# design.net
KiCad netlist of a schematic drawn in EasyEDA Pro
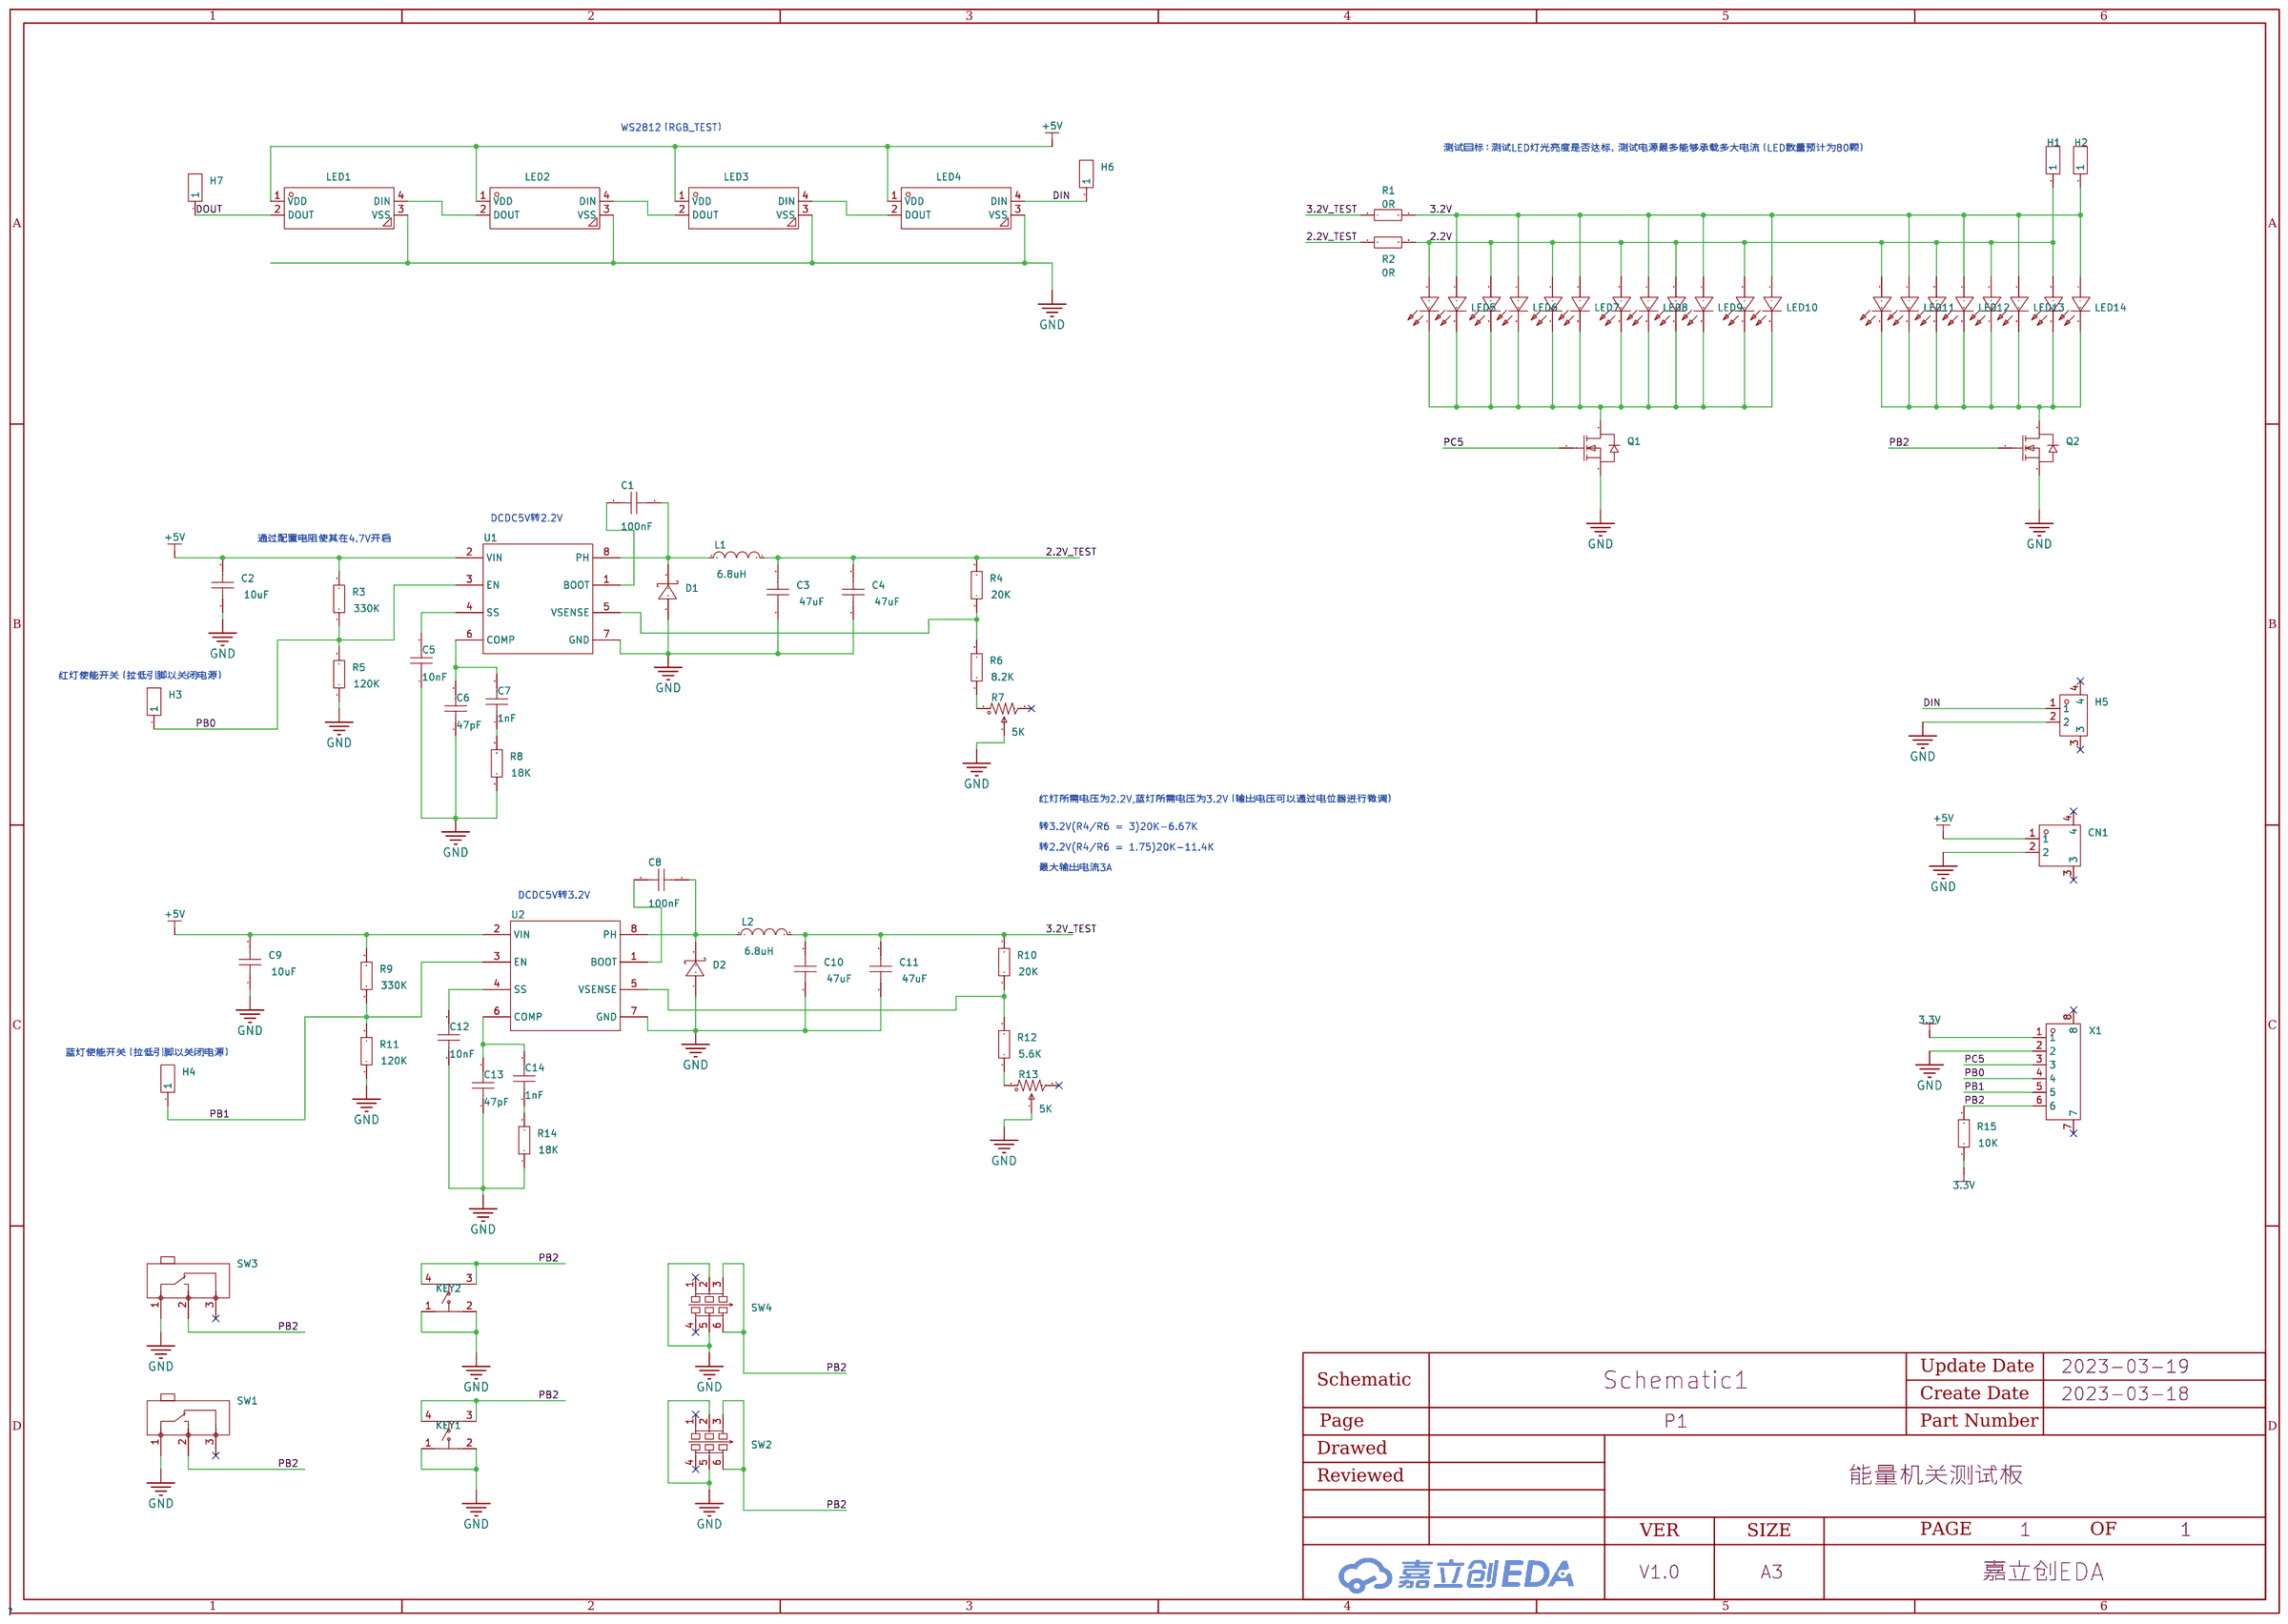
[diagram p0: schematic sheet]

(export (version "E")
  (design (tool "Eeschema 10.0.6"))
  (components
    (comp (ref "C1")
      (value "100nF")
      (footprint "easyedapro:C0603")
      (libsource (lib "easyedapro") (part "CapAcitance"))
    )
    (comp (ref "C2")
      (value "10uF")
      (footprint "easyedapro:C0603")
      (description "容值:10uF;精度:±20%;额定电压:25V;材质(温度系数):X5R;")
      (fields
        (field (name "Manufacturer Part") "CL10A106MA8NRNC")
        (field (name "Manufacturer") "SAMSUNG(三星)")
      )
      (libsource (lib "easyedapro") (part "CL10A106MA8NRNC"))
    )
    (comp (ref "C3")
      (value "47uF")
      (footprint "easyedapro:C1206")
      (description "容值:47uF;精度:±20%;额定电压:10V;材质(温度系数):X5R;")
      (fields
        (field (name "Manufacturer Part") "CL31A476MPHNNNE")
        (field (name "Manufacturer") "SAMSUNG(三星)")
      )
      (libsource (lib "easyedapro") (part "CL31A476MPHNNNE"))
    )
    (comp (ref "C4")
      (value "47uF")
      (footprint "easyedapro:C1206")
      (description "容值:47uF;精度:±20%;额定电压:10V;材质(温度系数):X5R;")
      (fields
        (field (name "Manufacturer Part") "CL31A476MPHNNNE")
        (field (name "Manufacturer") "SAMSUNG(三星)")
      )
      (libsource (lib "easyedapro") (part "CL31A476MPHNNNE"))
    )
    (comp (ref "C5")
      (value "10nF")
      (footprint "easyedapro:C0603")
      (libsource (lib "easyedapro") (part "CapAcitance"))
    )
    (comp (ref "C6")
      (value "47pF")
      (footprint "easyedapro:C0603")
      (libsource (lib "easyedapro") (part "CapAcitance"))
    )
    (comp (ref "C7")
      (value "1nF")
      (footprint "easyedapro:C0603")
      (libsource (lib "easyedapro") (part "CapAcitance"))
    )
    (comp (ref "C8")
      (value "100nF")
      (footprint "easyedapro:C0603")
      (libsource (lib "easyedapro") (part "CapAcitance"))
    )
    (comp (ref "C9")
      (value "10uF")
      (footprint "easyedapro:C0603")
      (libsource (lib "easyedapro") (part "CapAcitance"))
    )
    (comp (ref "C10")
      (value "47uF")
      (footprint "easyedapro:C1206")
      (description "容值:47uF;精度:±20%;额定电压:10V;材质(温度系数):X5R;")
      (fields
        (field (name "Manufacturer Part") "CL31A476MPHNNNE")
        (field (name "Manufacturer") "SAMSUNG(三星)")
      )
      (libsource (lib "easyedapro") (part "CL31A476MPHNNNE"))
    )
    (comp (ref "C11")
      (value "47uF")
      (footprint "easyedapro:C1206")
      (description "容值:47uF;精度:±20%;额定电压:10V;材质(温度系数):X5R;")
      (fields
        (field (name "Manufacturer Part") "CL31A476MPHNNNE")
        (field (name "Manufacturer") "SAMSUNG(三星)")
      )
      (libsource (lib "easyedapro") (part "CL31A476MPHNNNE"))
    )
    (comp (ref "C12")
      (value "10nF")
      (footprint "easyedapro:C0603")
      (libsource (lib "easyedapro") (part "CapAcitance"))
    )
    (comp (ref "C13")
      (value "47pF")
      (footprint "easyedapro:C0603")
      (libsource (lib "easyedapro") (part "CapAcitance"))
    )
    (comp (ref "C14")
      (value "1nF")
      (footprint "easyedapro:C0603")
      (libsource (lib "easyedapro") (part "CapAcitance"))
    )
    (comp (ref "CN1")
      (value "XT30PW-M")
      (footprint "easyedapro:CONN-TH_XT30PW-M")
      (description "Socket,DCsupply,XT30,male,PIN:2")
      (fields (field (name "Manufacturer") "AMASS(艾迈斯)"))
      (libsource (lib "easyedapro") (part "XT30PW-M"))
    )
    (comp (ref "D1")
      (value "SS54")
      (footprint "easyedapro:SMA_L4.4-W2.8-LS5.4-R-RD")
      (description "直流反向耐压(Vr):40V;平均整流电流(Io):5A;正向压降(Vf):550mV@5A;")
      (fields (field (name "Manufacturer") "MDD"))
      (libsource (lib "easyedapro") (part "SS54_C22452"))
    )
    (comp (ref "D2")
      (value "SS54")
      (footprint "easyedapro:SMA_L4.4-W2.8-LS5.4-R-RD")
      (description "直流反向耐压(Vr):40V;平均整流电流(Io):5A;正向压降(Vf):550mV@5A;")
      (fields (field (name "Manufacturer") "MDD"))
      (libsource (lib "easyedapro") (part "SS54_C22452"))
    )
    (comp (ref "H1")
      (value "~")
      (footprint "easyedapro:HDR-TH_1P-V-M_XKB_X4611WV-01I-C28D40")
      (libsource (lib "easyedapro") (part "HDR_1x1"))
    )
    (comp (ref "H2")
      (value "~")
      (footprint "easyedapro:HDR-TH_1P-V-M_XKB_X4611WV-01I-C28D40")
      (libsource (lib "easyedapro") (part "HDR_1x1"))
    )
    (comp (ref "H3")
      (value "~")
      (footprint "easyedapro:HDR-TH_1P-V-M_XKB_X4611WV-01I-C28D40")
      (libsource (lib "easyedapro") (part "HDR_1x1"))
    )
    (comp (ref "H4")
      (value "~")
      (footprint "easyedapro:HDR-TH_1P-V-M_XKB_X4611WV-01I-C28D40")
      (libsource (lib "easyedapro") (part "HDR_1x1"))
    )
    (comp (ref "H5")
      (value "GH1.25-2PWBPZ")
      (footprint "easyedapro:CONN-SMD_GH1.25-2PWBPZ")
      (fields (field (name "Manufacturer") "BOOMELE(博穆精密)"))
      (libsource (lib "easyedapro") (part "GH1.25-2PWBPZ"))
    )
    (comp (ref "H6")
      (value "~")
      (footprint "easyedapro:HDR-TH_1P-V-M_XKB_X4611WV-01I-C28D40")
      (libsource (lib "easyedapro") (part "HDR_1x1"))
    )
    (comp (ref "H7")
      (value "~")
      (footprint "easyedapro:HDR-TH_1P-V-M_XKB_X4611WV-01I-C28D40")
      (libsource (lib "easyedapro") (part "HDR_1x1"))
    )
    (comp (ref "KEY1")
      (value "B3F-4055")
      (footprint "easyedapro:KEY-TH_4P-L12.0-W12.0-P5.00-LS13.4-EH")
      (description "触点电流:50mA;额定电压(DC):24V;电路结构:单刀单掷;安装方式:直插;按钮形状:方形按钮;带灯:-;开关长度:12mm;开关宽度:12mm;开关高度:7.3mm;")
      (fields (field (name "Manufacturer") "OMRON(欧姆龙)"))
      (libsource (lib "easyedapro") (part "B3F-4055"))
    )
    (comp (ref "KEY2")
      (value "B3F-4055")
      (footprint "easyedapro:KEY-TH_4P-L12.0-W12.0-P5.00-LS13.4-EH")
      (description "触点电流:50mA;额定电压(DC):24V;电路结构:单刀单掷;安装方式:直插;按钮形状:方形按钮;带灯:-;开关长度:12mm;开关宽度:12mm;开关高度:7.3mm;")
      (fields (field (name "Manufacturer") "OMRON(欧姆龙)"))
      (libsource (lib "easyedapro") (part "B3F-4055"))
    )
    (comp (ref "L1")
      (value "6.8uH")
      (footprint "easyedapro:IND-SMD_L4.4-W4.2")
      (description "电感值:6.8uH;精度:±20%;额定电流:-;直流电阻(DCR):-;")
      (fields
        (field (name "Manufacturer Part") "SLO0420H6R8MTT")
        (field (name "Manufacturer") "Sunltech(韩国顺磁)")
      )
      (libsource (lib "easyedapro") (part "SLO0420H6R8MTT"))
    )
    (comp (ref "L2")
      (value "6.8uH")
      (footprint "easyedapro:IND-SMD_L4.4-W4.2")
      (description "电感值:6.8uH;精度:±20%;额定电流:-;直流电阻(DCR):-;")
      (fields
        (field (name "Manufacturer Part") "SLO0420H6R8MTT")
        (field (name "Manufacturer") "Sunltech(韩国顺磁)")
      )
      (libsource (lib "easyedapro") (part "SLO0420H6R8MTT"))
    )
    (comp (ref "LED1")
      (value "WS2812E")
      (footprint "easyedapro:LED-SMD_4P-L5.0-W5.0-BL_TC5050RGB")
      (description "发光颜色:RGB三色;透镜颜色:无色透明;")
      (fields (field (name "Manufacturer") "worldsemi"))
      (libsource (lib "easyedapro") (part "WS2812E"))
    )
    (comp (ref "LED2")
      (value "WS2812E")
      (footprint "easyedapro:LED-SMD_4P-L5.0-W5.0-BL_TC5050RGB")
      (description "发光颜色:RGB三色;透镜颜色:无色透明;")
      (fields (field (name "Manufacturer") "worldsemi"))
      (libsource (lib "easyedapro") (part "WS2812E"))
    )
    (comp (ref "LED3")
      (value "WS2812E")
      (footprint "easyedapro:LED-SMD_4P-L5.0-W5.0-BL_TC5050RGB")
      (description "发光颜色:RGB三色;透镜颜色:无色透明;")
      (fields (field (name "Manufacturer") "worldsemi"))
      (libsource (lib "easyedapro") (part "WS2812E"))
    )
    (comp (ref "LED4")
      (value "WS2812E")
      (footprint "easyedapro:LED-SMD_4P-L5.0-W5.0-BL_TC5050RGB")
      (description "发光颜色:RGB三色;透镜颜色:无色透明;")
      (fields (field (name "Manufacturer") "worldsemi"))
      (libsource (lib "easyedapro") (part "WS2812E"))
    )
    (comp (ref "LED5")
      (value "XL-3528SURUBC")
      (footprint "easyedapro:LED-SMD_4P-L3.2-W2.8-LS3.5-TL")
      (fields (field (name "Manufacturer") "XINGLIGHT(成兴光)"))
      (libsource (lib "easyedapro") (part "XL-3528SURUBC"))
    )
    (comp (ref "LED6")
      (value "XL-3528SURUBC")
      (footprint "easyedapro:LED-SMD_4P-L3.2-W2.8-LS3.5-TL")
      (fields (field (name "Manufacturer") "XINGLIGHT(成兴光)"))
      (libsource (lib "easyedapro") (part "XL-3528SURUBC"))
    )
    (comp (ref "LED7")
      (value "XL-3528SURUBC")
      (footprint "easyedapro:LED-SMD_4P-L3.2-W2.8-LS3.5-TL")
      (fields (field (name "Manufacturer") "XINGLIGHT(成兴光)"))
      (libsource (lib "easyedapro") (part "XL-3528SURUBC"))
    )
    (comp (ref "LED8")
      (value "XL-3528SURUBC")
      (footprint "easyedapro:LED-SMD_4P-L3.2-W2.8-LS3.5-TL")
      (fields (field (name "Manufacturer") "XINGLIGHT(成兴光)"))
      (libsource (lib "easyedapro") (part "XL-3528SURUBC"))
    )
    (comp (ref "LED9")
      (value "XL-3528SURUBC")
      (footprint "easyedapro:LED-SMD_4P-L3.2-W2.8-LS3.5-TL")
      (fields (field (name "Manufacturer") "XINGLIGHT(成兴光)"))
      (libsource (lib "easyedapro") (part "XL-3528SURUBC"))
    )
    (comp (ref "LED10")
      (value "XL-3528SURUBC")
      (footprint "easyedapro:LED-SMD_4P-L3.2-W2.8-LS3.5-TL")
      (fields (field (name "Manufacturer") "XINGLIGHT(成兴光)"))
      (libsource (lib "easyedapro") (part "XL-3528SURUBC"))
    )
    (comp (ref "LED11")
      (value "XL-3528SURUBC")
      (footprint "easyedapro:LED-SMD_4P-L3.2-W2.8-LS3.5-TL")
      (fields (field (name "Manufacturer") "XINGLIGHT(成兴光)"))
      (libsource (lib "easyedapro") (part "XL-3528SURUBC"))
    )
    (comp (ref "LED12")
      (value "XL-3528SURUBC")
      (footprint "easyedapro:LED-SMD_4P-L3.2-W2.8-LS3.5-TL")
      (fields (field (name "Manufacturer") "XINGLIGHT(成兴光)"))
      (libsource (lib "easyedapro") (part "XL-3528SURUBC"))
    )
    (comp (ref "LED13")
      (value "XL-3528SURUBC")
      (footprint "easyedapro:LED-SMD_4P-L3.2-W2.8-LS3.5-TL")
      (fields (field (name "Manufacturer") "XINGLIGHT(成兴光)"))
      (libsource (lib "easyedapro") (part "XL-3528SURUBC"))
    )
    (comp (ref "LED14")
      (value "XL-3528SURUBC")
      (footprint "easyedapro:LED-SMD_4P-L3.2-W2.8-LS3.5-TL")
      (fields (field (name "Manufacturer") "XINGLIGHT(成兴光)"))
      (libsource (lib "easyedapro") (part "XL-3528SURUBC"))
    )
    (comp (ref "Q1")
      (value "AO3400A")
      (footprint "easyedapro:SOT-23-3_L2.9-W1.6-P1.90-LS2.8-BR")
      (fields (field (name "Manufacturer") "AOS"))
      (libsource (lib "easyedapro") (part "AO3400A"))
    )
    (comp (ref "Q2")
      (value "AO3400A")
      (footprint "easyedapro:SOT-23-3_L2.9-W1.6-P1.90-LS2.8-BR")
      (fields (field (name "Manufacturer") "AOS"))
      (libsource (lib "easyedapro") (part "AO3400A"))
    )
    (comp (ref "R1") (value "0R") (footprint "easyedapro:R0603") (libsource (lib "easyedapro") (part "电阻")))
    (comp (ref "R2") (value "0R") (footprint "easyedapro:R0603") (libsource (lib "easyedapro") (part "电阻")))
    (comp (ref "R3") (value "330K") (footprint "easyedapro:R0603") (libsource (lib "easyedapro") (part "电阻")))
    (comp (ref "R4") (value "20K") (footprint "easyedapro:R0603") (libsource (lib "easyedapro") (part "电阻")))
    (comp (ref "R5") (value "120K") (footprint "easyedapro:R0603") (libsource (lib "easyedapro") (part "电阻")))
    (comp (ref "R6") (value "8.2K") (footprint "easyedapro:R0603") (libsource (lib "easyedapro") (part "电阻")))
    (comp (ref "R7")
      (value "5K")
      (footprint "easyedapro:RES-ADJ-SMD_3P-L3.0-W3.8-P1.75-BR")
      (description "阻值:10kΩ;精度:±25%;功率:150mW;圈数:-;额定电压:-;")
      (fields (field (name "Manufacturer Part") "TC33X-2-103E") (field (name "Manufacturer") "BOURNS"))
      (libsource (lib "easyedapro") (part "TC33X-2-103E"))
    )
    (comp (ref "R8") (value "18K") (footprint "easyedapro:R0603") (libsource (lib "easyedapro") (part "电阻")))
    (comp (ref "R9") (value "330K") (footprint "easyedapro:R0603") (libsource (lib "easyedapro") (part "电阻")))
    (comp (ref "R10") (value "20K") (footprint "easyedapro:R0603") (libsource (lib "easyedapro") (part "电阻")))
    (comp (ref "R11")
      (value "120K")
      (footprint "easyedapro:R0603")
      (libsource (lib "easyedapro") (part "电阻"))
    )
    (comp (ref "R12")
      (value "5.6K")
      (footprint "easyedapro:R0603")
      (libsource (lib "easyedapro") (part "电阻"))
    )
    (comp (ref "R13")
      (value "5K")
      (footprint "easyedapro:RES-ADJ-SMD_3P-L3.0-W3.8-P1.75-BR")
      (description "阻值:10kΩ;精度:±25%;功率:150mW;圈数:-;额定电压:-;")
      (fields (field (name "Manufacturer Part") "TC33X-2-103E") (field (name "Manufacturer") "BOURNS"))
      (libsource (lib "easyedapro") (part "TC33X-2-103E"))
    )
    (comp (ref "R14") (value "18K") (footprint "easyedapro:R0603") (libsource (lib "easyedapro") (part "电阻")))
    (comp (ref "R15") (value "10K") (footprint "easyedapro:R0603") (libsource (lib "easyedapro") (part "电阻")))
    (comp (ref "SW1")
      (value "D2F-F")
      (footprint "easyedapro:SW-TH_D2F-F")
      (description "额定电流(DC):-;额定电压(DC):-;额定电流(AC):1A;额定电压(AC):125V;电路结构:单刀双掷;")
      (fields (field (name "Manufacturer") "OMRON(欧姆龙)"))
      (libsource (lib "easyedapro") (part "D2F-F"))
    )
    (comp (ref "SW2")
      (value "BTSA-L-P-16")
      (footprint "easyedapro:SW-TH_BTSA-X-P-16")
      (fields (field (name "Manufacturer") "ROCPU Switches(台普)"))
      (libsource (lib "easyedapro") (part "BTSA-L-P-16"))
    )
    (comp (ref "SW3")
      (value "D2F-F")
      (footprint "easyedapro:SW-TH_D2F-F")
      (description "额定电流(DC):-;额定电压(DC):-;额定电流(AC):1A;额定电压(AC):125V;电路结构:单刀双掷;")
      (fields (field (name "Manufacturer") "OMRON(欧姆龙)"))
      (libsource (lib "easyedapro") (part "D2F-F"))
    )
    (comp (ref "SW4")
      (value "BTSA-L-P-16")
      (footprint "easyedapro:SW-TH_BTSA-X-P-16")
      (fields (field (name "Manufacturer") "ROCPU Switches(台普)"))
      (libsource (lib "easyedapro") (part "BTSA-L-P-16"))
    )
    (comp (ref "U1")
      (value "TPS54331DR")
      (footprint "easyedapro:SOIC-8_L5.0-W4.0-P1.27-LS6.0-BL")
      (description "功能类型:降压型;同步整流:-;输出通道数:-;拓扑结构:-;输入电压:-;输出电流(最大值):-;开关频率:-;")
      (fields (field (name "Manufacturer") "TI(德州仪器)"))
      (libsource (lib "easyedapro") (part "TPS54331DR"))
    )
    (comp (ref "U2")
      (value "TPS54331DR")
      (footprint "easyedapro:SOIC-8_L5.0-W4.0-P1.27-LS6.0-BL")
      (description "功能类型:降压型;同步整流:-;输出通道数:-;拓扑结构:-;输入电压:-;输出电流(最大值):-;开关频率:-;")
      (fields (field (name "Manufacturer") "TI(德州仪器)"))
      (libsource (lib "easyedapro") (part "TPS54331DR"))
    )
    (comp (ref "X1")
      (value "GH125-S06DCA-00")
      (footprint "easyedapro:CONN-SMD_6P-P1.25_JUSHUO_GH125-S06DCA-00")
      (description "参考系列:GH;间距:1.25mm;插针结构:1x6P;排数:1;每排PIN数:6;行距:-;公母:公型插针;安装方式:卧贴;额定电流:1A;工作温度范围:-25°C~+85°C;")
      (fields (field (name "Manufacturer") "JS(钜硕电子)"))
      (libsource (lib "easyedapro") (part "GH125-S06DCA-00"))
    )
  )
  (nets
    (net (code "1") (name "+5V") (class "Default")
      (node (ref "C2") (pin "2") (pinfunction "2_2") (pintype "input"))
      (node (ref "C9") (pin "2") (pinfunction "2_2") (pintype "input"))
      (node (ref "CN1") (pin "1") (pinfunction "1_1") (pintype "input"))
      (node (ref "LED1") (pin "1") (pinfunction "VDD_1") (pintype "input"))
      (node (ref "LED2") (pin "1") (pinfunction "VDD_1") (pintype "input"))
      (node (ref "LED3") (pin "1") (pinfunction "VDD_1") (pintype "input"))
      (node (ref "LED4") (pin "1") (pinfunction "VDD_1") (pintype "input"))
      (node (ref "R3") (pin "2") (pinfunction "2_2") (pintype "input"))
      (node (ref "R9") (pin "2") (pinfunction "2_2") (pintype "input"))
      (node (ref "U1") (pin "2") (pinfunction "VIN_2") (pintype "input"))
      (node (ref "U2") (pin "2") (pinfunction "VIN_2") (pintype "input"))
    )
    (net (code "2") (name "/2.2V") (class "Default")
      (node (ref "H1") (pin "1") (pinfunction "1_1") (pintype "unspecified"))
      (node (ref "LED10") (pin "2") (pinfunction "2_2") (pintype "input"))
      (node (ref "LED11") (pin "2") (pinfunction "2_2") (pintype "input"))
      (node (ref "LED12") (pin "2") (pinfunction "2_2") (pintype "input"))
      (node (ref "LED13") (pin "2") (pinfunction "2_2") (pintype "input"))
      (node (ref "LED14") (pin "2") (pinfunction "2_2") (pintype "input"))
      (node (ref "LED5") (pin "2") (pinfunction "2_2") (pintype "input"))
      (node (ref "LED6") (pin "2") (pinfunction "2_2") (pintype "input"))
      (node (ref "LED7") (pin "2") (pinfunction "2_2") (pintype "input"))
      (node (ref "LED8") (pin "2") (pinfunction "2_2") (pintype "input"))
      (node (ref "LED9") (pin "2") (pinfunction "2_2") (pintype "input"))
      (node (ref "R2") (pin "2") (pinfunction "2_2") (pintype "input"))
    )
    (net (code "3") (name "/2.2V_TEST") (class "Default")
      (node (ref "C3") (pin "2") (pinfunction "2_2") (pintype "input"))
      (node (ref "C4") (pin "2") (pinfunction "2_2") (pintype "input"))
      (node (ref "L1") (pin "2") (pinfunction "2_2") (pintype "input"))
      (node (ref "R2") (pin "1") (pinfunction "1_1") (pintype "input"))
      (node (ref "R4") (pin "2") (pinfunction "2_2") (pintype "input"))
    )
    (net (code "4") (name "/3.2V") (class "Default")
      (node (ref "H2") (pin "1") (pinfunction "1_1") (pintype "unspecified"))
      (node (ref "LED10") (pin "4") (pinfunction "4_4") (pintype "input"))
      (node (ref "LED11") (pin "4") (pinfunction "4_4") (pintype "input"))
      (node (ref "LED12") (pin "4") (pinfunction "4_4") (pintype "input"))
      (node (ref "LED13") (pin "4") (pinfunction "4_4") (pintype "input"))
      (node (ref "LED14") (pin "4") (pinfunction "4_4") (pintype "input"))
      (node (ref "LED5") (pin "4") (pinfunction "4_4") (pintype "input"))
      (node (ref "LED6") (pin "4") (pinfunction "4_4") (pintype "input"))
      (node (ref "LED7") (pin "4") (pinfunction "4_4") (pintype "input"))
      (node (ref "LED8") (pin "4") (pinfunction "4_4") (pintype "input"))
      (node (ref "LED9") (pin "4") (pinfunction "4_4") (pintype "input"))
      (node (ref "R1") (pin "2") (pinfunction "2_2") (pintype "input"))
    )
    (net (code "5") (name "/3.2V_TEST") (class "Default")
      (node (ref "C10") (pin "2") (pinfunction "2_2") (pintype "input"))
      (node (ref "C11") (pin "2") (pinfunction "2_2") (pintype "input"))
      (node (ref "L2") (pin "2") (pinfunction "2_2") (pintype "input"))
      (node (ref "R1") (pin "1") (pinfunction "1_1") (pintype "input"))
      (node (ref "R10") (pin "2") (pinfunction "2_2") (pintype "input"))
    )
    (net (code "6") (name "/DIN") (class "Default")
      (node (ref "H5") (pin "1") (pinfunction "1_1") (pintype "input"))
      (node (ref "H6") (pin "1") (pinfunction "1_1") (pintype "unspecified"))
      (node (ref "LED4") (pin "4") (pinfunction "DIN_4") (pintype "input"))
    )
    (net (code "7") (name "/DOUT") (class "Default")
      (node (ref "H7") (pin "1") (pinfunction "1_1") (pintype "unspecified"))
      (node (ref "LED1") (pin "2") (pinfunction "DOUT_2") (pintype "input"))
    )
    (net (code "8") (name "/PB0") (class "Default")
      (node (ref "H3") (pin "1") (pinfunction "1_1") (pintype "unspecified"))
      (node (ref "R3") (pin "1") (pinfunction "1_1") (pintype "input"))
      (node (ref "R5") (pin "2") (pinfunction "2_2") (pintype "input"))
      (node (ref "U1") (pin "3") (pinfunction "EN_3") (pintype "input"))
      (node (ref "X1") (pin "4") (pinfunction "4_4") (pintype "input"))
    )
    (net (code "9") (name "/PB1") (class "Default")
      (node (ref "H4") (pin "1") (pinfunction "1_1") (pintype "unspecified"))
      (node (ref "R11") (pin "2") (pinfunction "2_2") (pintype "input"))
      (node (ref "R9") (pin "1") (pinfunction "1_1") (pintype "input"))
      (node (ref "U2") (pin "3") (pinfunction "EN_3") (pintype "input"))
      (node (ref "X1") (pin "5") (pinfunction "5_5") (pintype "input"))
    )
    (net (code "10") (name "/PB2") (class "Default")
      (node (ref "KEY1") (pin "3") (pinfunction "3_3") (pintype "input"))
      (node (ref "KEY1") (pin "4") (pinfunction "4_4") (pintype "input"))
      (node (ref "KEY2") (pin "3") (pinfunction "3_3") (pintype "input"))
      (node (ref "KEY2") (pin "4") (pinfunction "4_4") (pintype "input"))
      (node (ref "Q2") (pin "1") (pinfunction "G_1") (pintype "input"))
      (node (ref "R15") (pin "2") (pinfunction "2_2") (pintype "input"))
      (node (ref "SW1") (pin "2") (pinfunction "2_2") (pintype "input"))
      (node (ref "SW2") (pin "3") (pinfunction "3_3") (pintype "input"))
      (node (ref "SW2") (pin "6") (pinfunction "6_6") (pintype "input"))
      (node (ref "SW3") (pin "2") (pinfunction "2_2") (pintype "input"))
      (node (ref "SW4") (pin "3") (pinfunction "3_3") (pintype "input"))
      (node (ref "SW4") (pin "6") (pinfunction "6_6") (pintype "input"))
      (node (ref "X1") (pin "6") (pinfunction "6_6") (pintype "input"))
    )
    (net (code "11") (name "/PC5") (class "Default")
      (node (ref "Q1") (pin "1") (pinfunction "G_1") (pintype "input"))
      (node (ref "X1") (pin "3") (pinfunction "3_3") (pintype "input"))
    )
    (net (code "12") (name "3.3V") (class "Default")
      (node (ref "R15") (pin "1") (pinfunction "1_1") (pintype "input"))
      (node (ref "X1") (pin "1") (pinfunction "1_1") (pintype "input"))
    )
    (net (code "13") (name "GND") (class "Default")
      (node (ref "C10") (pin "1") (pinfunction "1_1") (pintype "input"))
      (node (ref "C11") (pin "1") (pinfunction "1_1") (pintype "input"))
      (node (ref "C12") (pin "1") (pinfunction "1_1") (pintype "input"))
      (node (ref "C13") (pin "1") (pinfunction "1_1") (pintype "input"))
      (node (ref "C2") (pin "1") (pinfunction "1_1") (pintype "input"))
      (node (ref "C3") (pin "1") (pinfunction "1_1") (pintype "input"))
      (node (ref "C4") (pin "1") (pinfunction "1_1") (pintype "input"))
      (node (ref "C5") (pin "1") (pinfunction "1_1") (pintype "input"))
      (node (ref "C6") (pin "1") (pinfunction "1_1") (pintype "input"))
      (node (ref "C9") (pin "1") (pinfunction "1_1") (pintype "input"))
      (node (ref "CN1") (pin "2") (pinfunction "2_2") (pintype "input"))
      (node (ref "D1") (pin "1") (pinfunction "A_1") (pintype "input"))
      (node (ref "D2") (pin "1") (pinfunction "A_1") (pintype "input"))
      (node (ref "H5") (pin "2") (pinfunction "2_2") (pintype "input"))
      (node (ref "KEY1") (pin "1") (pinfunction "1_1") (pintype "input"))
      (node (ref "KEY1") (pin "2") (pinfunction "2_2") (pintype "input"))
      (node (ref "KEY2") (pin "1") (pinfunction "1_1") (pintype "input"))
      (node (ref "KEY2") (pin "2") (pinfunction "2_2") (pintype "input"))
      (node (ref "LED1") (pin "3") (pinfunction "VSS_3") (pintype "input"))
      (node (ref "LED2") (pin "3") (pinfunction "VSS_3") (pintype "input"))
      (node (ref "LED3") (pin "3") (pinfunction "VSS_3") (pintype "input"))
      (node (ref "LED4") (pin "3") (pinfunction "VSS_3") (pintype "input"))
      (node (ref "Q1") (pin "2") (pinfunction "S_2") (pintype "input"))
      (node (ref "Q2") (pin "2") (pinfunction "S_2") (pintype "input"))
      (node (ref "R11") (pin "1") (pinfunction "1_1") (pintype "input"))
      (node (ref "R13") (pin "2") (pinfunction "2_2") (pintype "input"))
      (node (ref "R14") (pin "1") (pinfunction "1_1") (pintype "input"))
      (node (ref "R5") (pin "1") (pinfunction "1_1") (pintype "input"))
      (node (ref "R7") (pin "2") (pinfunction "2_2") (pintype "input"))
      (node (ref "R8") (pin "1") (pinfunction "1_1") (pintype "input"))
      (node (ref "SW1") (pin "1") (pinfunction "1_1") (pintype "input"))
      (node (ref "SW2") (pin "2") (pinfunction "2_2") (pintype "input"))
      (node (ref "SW2") (pin "5") (pinfunction "5_5") (pintype "input"))
      (node (ref "SW3") (pin "1") (pinfunction "1_1") (pintype "input"))
      (node (ref "SW4") (pin "2") (pinfunction "2_2") (pintype "input"))
      (node (ref "SW4") (pin "5") (pinfunction "5_5") (pintype "input"))
      (node (ref "U1") (pin "7") (pinfunction "GND_7") (pintype "input"))
      (node (ref "U2") (pin "7") (pinfunction "GND_7") (pintype "input"))
      (node (ref "X1") (pin "2") (pinfunction "2_2") (pintype "input"))
    )
    (net (code "14") (name "Net-(C7-Pad1)") (class "Default")
      (node (ref "C7") (pin "1") (pinfunction "1_1") (pintype "input"))
      (node (ref "R8") (pin "2") (pinfunction "2_2") (pintype "input"))
    )
    (net (code "15") (name "Net-(C14-Pad1)") (class "Default")
      (node (ref "C14") (pin "1") (pinfunction "1_1") (pintype "input"))
      (node (ref "R14") (pin "2") (pinfunction "2_2") (pintype "input"))
    )
    (net (code "16") (name "Net-(D1-K)") (class "Default")
      (node (ref "C1") (pin "1") (pinfunction "1_1") (pintype "input"))
      (node (ref "D1") (pin "2") (pinfunction "K_2") (pintype "input"))
      (node (ref "L1") (pin "1") (pinfunction "1_1") (pintype "input"))
      (node (ref "U1") (pin "8") (pinfunction "PH_8") (pintype "input"))
    )
    (net (code "17") (name "Net-(D2-K)") (class "Default")
      (node (ref "C8") (pin "1") (pinfunction "1_1") (pintype "input"))
      (node (ref "D2") (pin "2") (pinfunction "K_2") (pintype "input"))
      (node (ref "L2") (pin "1") (pinfunction "1_1") (pintype "input"))
      (node (ref "U2") (pin "8") (pinfunction "PH_8") (pintype "input"))
    )
    (net (code "18") (name "Net-(LED1-DIN)") (class "Default")
      (node (ref "LED1") (pin "4") (pinfunction "DIN_4") (pintype "input"))
      (node (ref "LED2") (pin "2") (pinfunction "DOUT_2") (pintype "input"))
    )
    (net (code "19") (name "Net-(LED2-DIN)") (class "Default")
      (node (ref "LED2") (pin "4") (pinfunction "DIN_4") (pintype "input"))
      (node (ref "LED3") (pin "2") (pinfunction "DOUT_2") (pintype "input"))
    )
    (net (code "20") (name "Net-(LED3-DIN)") (class "Default")
      (node (ref "LED3") (pin "4") (pinfunction "DIN_4") (pintype "input"))
      (node (ref "LED4") (pin "2") (pinfunction "DOUT_2") (pintype "input"))
    )
    (net (code "21") (name "Net-(Q1-D)") (class "Default")
      (node (ref "LED10") (pin "1") (pinfunction "1_1") (pintype "input"))
      (node (ref "LED10") (pin "3") (pinfunction "3_3") (pintype "input"))
      (node (ref "LED5") (pin "1") (pinfunction "1_1") (pintype "input"))
      (node (ref "LED5") (pin "3") (pinfunction "3_3") (pintype "input"))
      (node (ref "LED6") (pin "1") (pinfunction "1_1") (pintype "input"))
      (node (ref "LED6") (pin "3") (pinfunction "3_3") (pintype "input"))
      (node (ref "LED7") (pin "1") (pinfunction "1_1") (pintype "input"))
      (node (ref "LED7") (pin "3") (pinfunction "3_3") (pintype "input"))
      (node (ref "LED8") (pin "1") (pinfunction "1_1") (pintype "input"))
      (node (ref "LED8") (pin "3") (pinfunction "3_3") (pintype "input"))
      (node (ref "LED9") (pin "1") (pinfunction "1_1") (pintype "input"))
      (node (ref "LED9") (pin "3") (pinfunction "3_3") (pintype "input"))
      (node (ref "Q1") (pin "3") (pinfunction "D_3") (pintype "input"))
    )
    (net (code "22") (name "Net-(Q2-D)") (class "Default")
      (node (ref "LED11") (pin "1") (pinfunction "1_1") (pintype "input"))
      (node (ref "LED11") (pin "3") (pinfunction "3_3") (pintype "input"))
      (node (ref "LED12") (pin "1") (pinfunction "1_1") (pintype "input"))
      (node (ref "LED12") (pin "3") (pinfunction "3_3") (pintype "input"))
      (node (ref "LED13") (pin "1") (pinfunction "1_1") (pintype "input"))
      (node (ref "LED13") (pin "3") (pinfunction "3_3") (pintype "input"))
      (node (ref "LED14") (pin "1") (pinfunction "1_1") (pintype "input"))
      (node (ref "LED14") (pin "3") (pinfunction "3_3") (pintype "input"))
      (node (ref "Q2") (pin "3") (pinfunction "D_3") (pintype "input"))
    )
    (net (code "23") (name "Net-(R6-Pad1)") (class "Default")
      (node (ref "R6") (pin "1") (pinfunction "1_1") (pintype "input"))
      (node (ref "R7") (pin "1") (pinfunction "1_1") (pintype "input"))
    )
    (net (code "24") (name "Net-(R12-Pad1)") (class "Default")
      (node (ref "R12") (pin "1") (pinfunction "1_1") (pintype "input"))
      (node (ref "R13") (pin "1") (pinfunction "1_1") (pintype "input"))
    )
    (net (code "25") (name "Net-(U1-BOOT)") (class "Default")
      (node (ref "C1") (pin "2") (pinfunction "2_2") (pintype "input"))
      (node (ref "U1") (pin "1") (pinfunction "BOOT_1") (pintype "input"))
    )
    (net (code "26") (name "Net-(U1-COMP)") (class "Default")
      (node (ref "C6") (pin "2") (pinfunction "2_2") (pintype "input"))
      (node (ref "C7") (pin "2") (pinfunction "2_2") (pintype "input"))
      (node (ref "U1") (pin "6") (pinfunction "COMP_6") (pintype "input"))
    )
    (net (code "27") (name "Net-(U1-SS)") (class "Default")
      (node (ref "C5") (pin "2") (pinfunction "2_2") (pintype "input"))
      (node (ref "U1") (pin "4") (pinfunction "SS_4") (pintype "input"))
    )
    (net (code "28") (name "Net-(U1-VSENSE)") (class "Default")
      (node (ref "R4") (pin "1") (pinfunction "1_1") (pintype "input"))
      (node (ref "R6") (pin "2") (pinfunction "2_2") (pintype "input"))
      (node (ref "U1") (pin "5") (pinfunction "VSENSE_5") (pintype "input"))
    )
    (net (code "29") (name "Net-(U2-BOOT)") (class "Default")
      (node (ref "C8") (pin "2") (pinfunction "2_2") (pintype "input"))
      (node (ref "U2") (pin "1") (pinfunction "BOOT_1") (pintype "input"))
    )
    (net (code "30") (name "Net-(U2-COMP)") (class "Default")
      (node (ref "C13") (pin "2") (pinfunction "2_2") (pintype "input"))
      (node (ref "C14") (pin "2") (pinfunction "2_2") (pintype "input"))
      (node (ref "U2") (pin "6") (pinfunction "COMP_6") (pintype "input"))
    )
    (net (code "31") (name "Net-(U2-SS)") (class "Default")
      (node (ref "C12") (pin "2") (pinfunction "2_2") (pintype "input"))
      (node (ref "U2") (pin "4") (pinfunction "SS_4") (pintype "input"))
    )
    (net (code "32") (name "Net-(U2-VSENSE)") (class "Default")
      (node (ref "R10") (pin "1") (pinfunction "1_1") (pintype "input"))
      (node (ref "R12") (pin "2") (pinfunction "2_2") (pintype "input"))
      (node (ref "U2") (pin "5") (pinfunction "VSENSE_5") (pintype "input"))
    )
    (net (code "33") (name "unconnected-(CN1-Pad3)") (class "Default")
      (node (ref "CN1") (pin "3") (pinfunction "3_3") (pintype "input+no_connect"))
    )
    (net (code "34") (name "unconnected-(CN1-Pad4)") (class "Default")
      (node (ref "CN1") (pin "4") (pinfunction "4_4") (pintype "input+no_connect"))
    )
    (net (code "35") (name "unconnected-(H5-Pad3)") (class "Default")
      (node (ref "H5") (pin "3") (pinfunction "3_3") (pintype "input+no_connect"))
    )
    (net (code "36") (name "unconnected-(H5-Pad4)") (class "Default")
      (node (ref "H5") (pin "4") (pinfunction "4_4") (pintype "input+no_connect"))
    )
    (net (code "37") (name "unconnected-(R7-Pad3)") (class "Default")
      (node (ref "R7") (pin "3") (pinfunction "3_3") (pintype "input+no_connect"))
    )
    (net (code "38") (name "unconnected-(R13-Pad3)") (class "Default")
      (node (ref "R13") (pin "3") (pinfunction "3_3") (pintype "input+no_connect"))
    )
    (net (code "39") (name "unconnected-(SW1-Pad3)") (class "Default")
      (node (ref "SW1") (pin "3") (pinfunction "3_3") (pintype "input+no_connect"))
    )
    (net (code "40") (name "unconnected-(SW2-Pad1)") (class "Default")
      (node (ref "SW2") (pin "1") (pinfunction "1_1") (pintype "input+no_connect"))
    )
    (net (code "41") (name "unconnected-(SW2-Pad4)") (class "Default")
      (node (ref "SW2") (pin "4") (pinfunction "4_4") (pintype "input+no_connect"))
    )
    (net (code "42") (name "unconnected-(SW3-Pad3)") (class "Default")
      (node (ref "SW3") (pin "3") (pinfunction "3_3") (pintype "input+no_connect"))
    )
    (net (code "43") (name "unconnected-(SW4-Pad1)") (class "Default")
      (node (ref "SW4") (pin "1") (pinfunction "1_1") (pintype "input+no_connect"))
    )
    (net (code "44") (name "unconnected-(SW4-Pad4)") (class "Default")
      (node (ref "SW4") (pin "4") (pinfunction "4_4") (pintype "input+no_connect"))
    )
    (net (code "45") (name "unconnected-(X1-Pad7)") (class "Default")
      (node (ref "X1") (pin "7") (pinfunction "7_7") (pintype "input+no_connect"))
    )
    (net (code "46") (name "unconnected-(X1-Pad8)") (class "Default")
      (node (ref "X1") (pin "8") (pinfunction "8_8") (pintype "input+no_connect"))
    )
  )
)
